# EE192_Sp17_Team01_combo.net
KiCad netlist of a schematic drawn in EAGLE
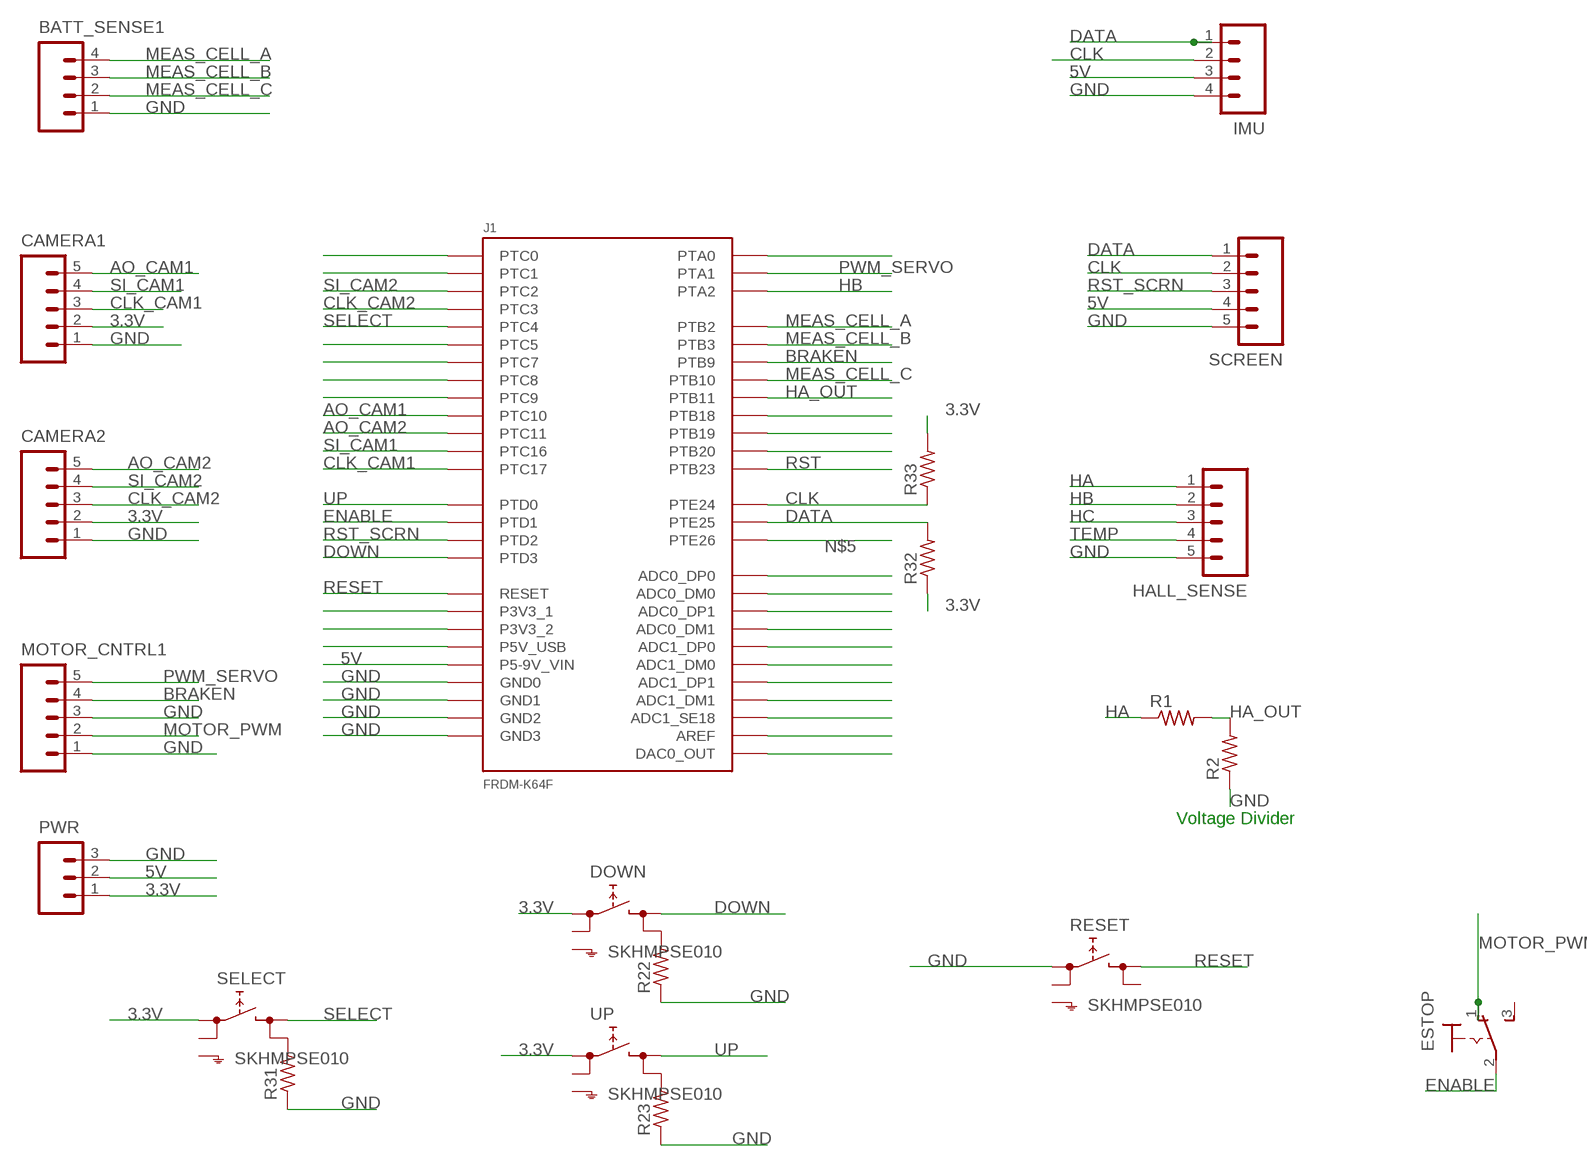
[diagram p0: schematic, sheet 1]
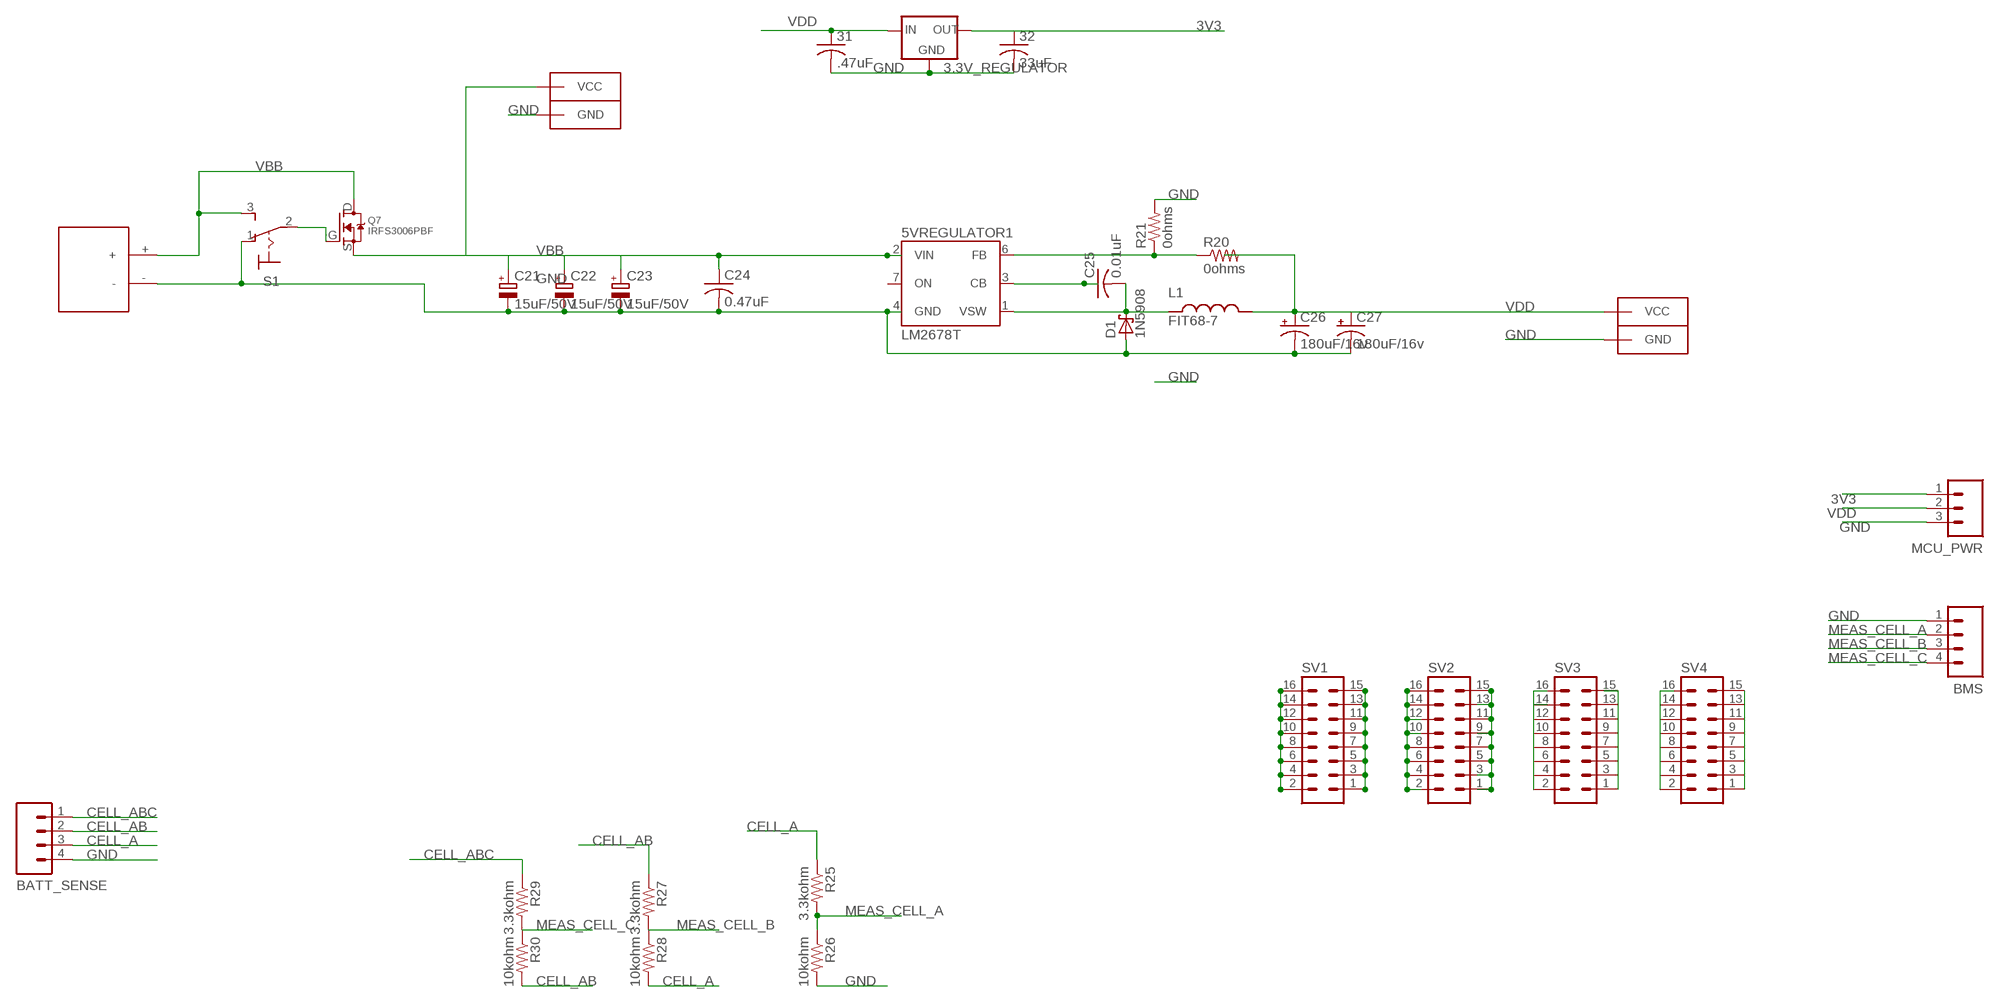
[diagram p1: schematic, sheet 3]
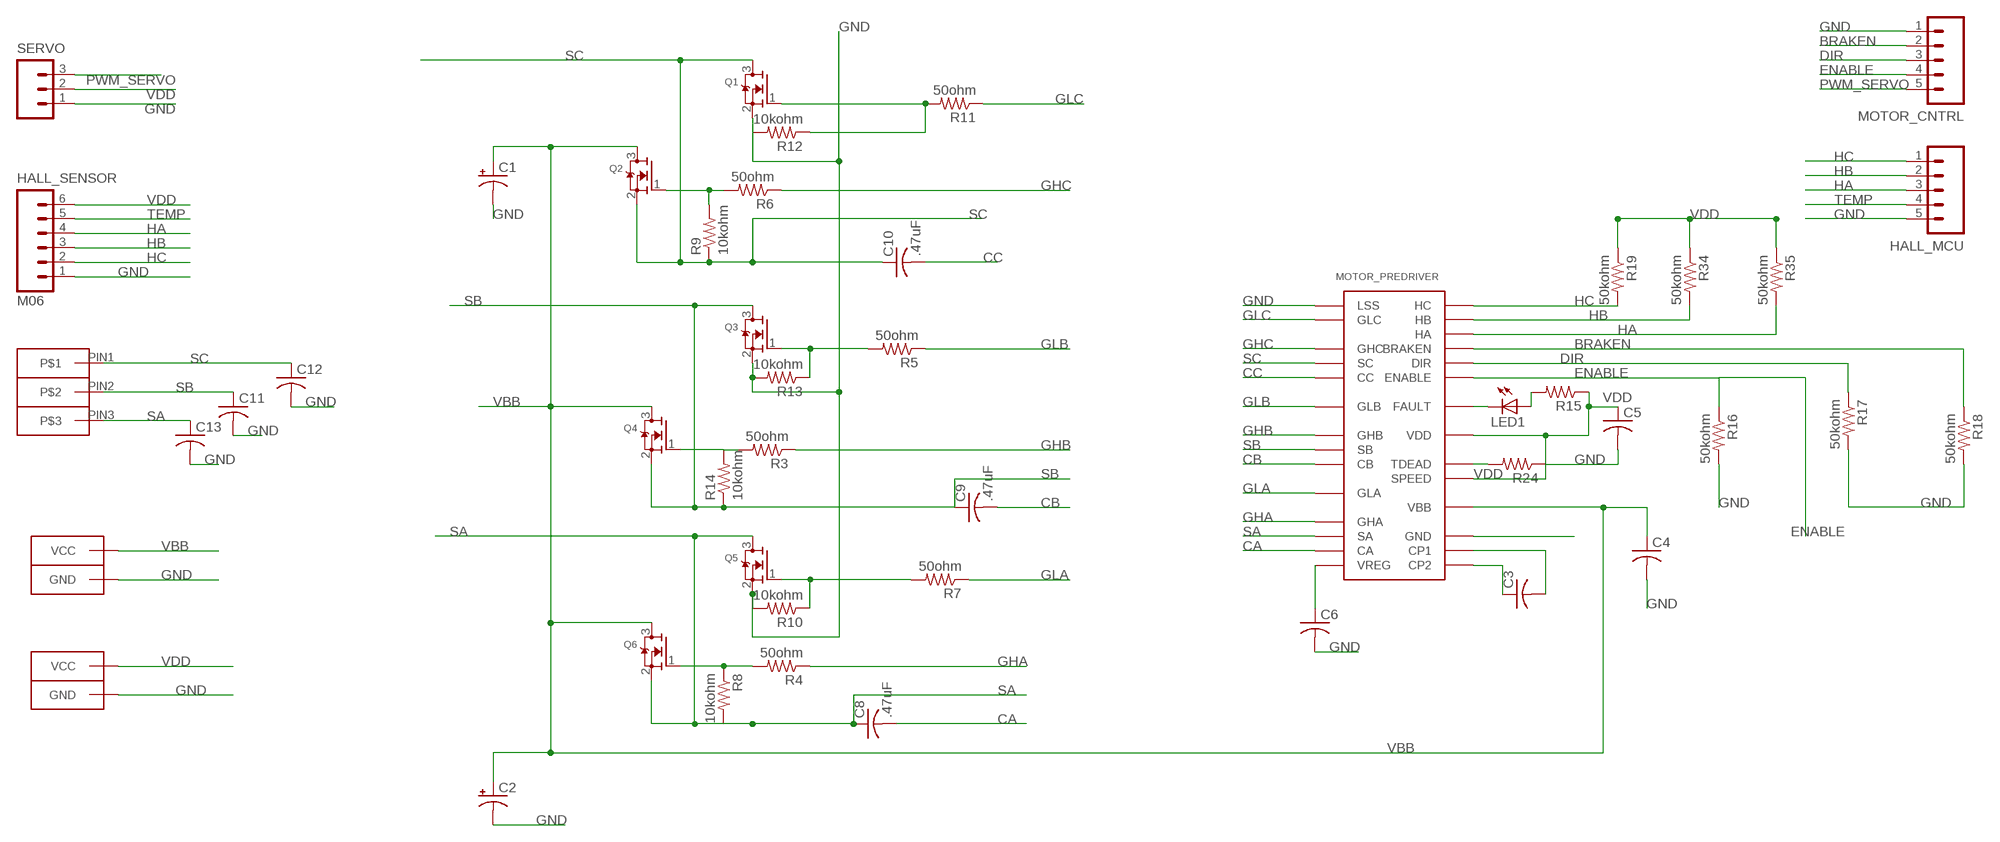
[diagram p2: schematic, sheet 4]

(export (version "E")
  (design (tool "Eeschema 10.0.6"))
  (components
    (comp (ref "C1")
      (value "CPOL-USE5-10.5")
      (footprint "eagle-import:E5-10,5")
      (libsource (lib "eagle-import") (part "CPOL-USE5-10.5"))
    )
    (comp (ref "C2")
      (value "CPOL-USE5-10.5")
      (footprint "eagle-import:E5-10,5")
      (libsource (lib "eagle-import") (part "CPOL-USE5-10.5"))
    )
    (comp (ref "C3")
      (value "C-USC0805")
      (footprint "eagle-import:C0805")
      (libsource (lib "eagle-import") (part "C-USC0805"))
    )
    (comp (ref "C4")
      (value "C-USC0805")
      (footprint "eagle-import:C0805")
      (libsource (lib "eagle-import") (part "C-USC0805"))
    )
    (comp (ref "C5")
      (value "C-USC0805")
      (footprint "eagle-import:C0805")
      (libsource (lib "eagle-import") (part "C-USC0805"))
    )
    (comp (ref "C6")
      (value "C-USC0805")
      (footprint "eagle-import:C0805")
      (libsource (lib "eagle-import") (part "C-USC0805"))
    )
    (comp (ref "C8")
      (value ".47uF")
      (footprint "eagle-import:C0805")
      (libsource (lib "eagle-import") (part "C-USC0805"))
    )
    (comp (ref "C9")
      (value ".47uF")
      (footprint "eagle-import:C0805")
      (libsource (lib "eagle-import") (part "C-USC0805"))
    )
    (comp (ref "C10")
      (value ".47uF")
      (footprint "eagle-import:C0805")
      (libsource (lib "eagle-import") (part "C-USC0805"))
    )
    (comp (ref "C11")
      (value "C-USC0805")
      (footprint "eagle-import:C0805")
      (libsource (lib "eagle-import") (part "C-USC0805"))
    )
    (comp (ref "C12")
      (value "C-USC0805")
      (footprint "eagle-import:C0805")
      (libsource (lib "eagle-import") (part "C-USC0805"))
    )
    (comp (ref "C13")
      (value "C-USC0805")
      (footprint "eagle-import:C0805")
      (libsource (lib "eagle-import") (part "C-USC0805"))
    )
    (comp (ref "CONN1")
      (value "ANDERSON_PP_DOUBLEVERTICAL")
      (footprint "eagle-import:ANDERSON_PP_DOUB_VERT")
      (libsource (lib "eagle-import") (part "ANDERSON_PP_DOUBLEVERTICAL"))
    )
    (comp (ref "CONN3")
      (value "ANDERSON_PP_DOUBLEVERTICAL")
      (footprint "eagle-import:ANDERSON_PP_DOUB_VERT")
      (libsource (lib "eagle-import") (part "ANDERSON_PP_DOUBLEVERTICAL"))
    )
    (comp (ref "HALL_MCU")
      (value "M05MTA")
      (footprint "eagle-import:1X05-MTA")
      (libsource (lib "eagle-import") (part "M05MTA"))
    )
    (comp (ref "HALL_SENSOR")
      (value "M06")
      (footprint "eagle-import:1X06-MTA")
      (libsource (lib "eagle-import") (part "M06"))
    )
    (comp (ref "LED1")
      (value "LEDCHIPLED_0805")
      (footprint "eagle-import:CHIPLED_0805")
      (libsource (lib "eagle-import") (part "LEDCHIPLED_0805"))
    )
    (comp (ref "MOTOR_CNTRL")
      (value "M05MTA")
      (footprint "eagle-import:1X05-MTA")
      (libsource (lib "eagle-import") (part "M05MTA"))
    )
    (comp (ref "MOTOR_PREDRIVER")
      (value "A4915SOCKET")
      (footprint "eagle-import:DIL28-6")
      (libsource (lib "eagle-import") (part "A4915SOCKET"))
    )
    (comp (ref "MOTOR_PWR1")
      (value "ANDERSON_PP_TRIPVERT")
      (footprint "eagle-import:ANDERSON_PP_TRIP_VERT")
      (libsource (lib "eagle-import") (part "ANDERSON_PP_TRIPVERT"))
    )
    (comp (ref "Q1")
      (value "IRFS3006PBFTO263PACKAGE")
      (footprint "eagle-import:TO263")
      (libsource (lib "eagle-import") (part "IRFS3006PBFTO263PACKAGE"))
    )
    (comp (ref "Q2")
      (value "IRFS3006PBFTO263PACKAGE")
      (footprint "eagle-import:TO263")
      (libsource (lib "eagle-import") (part "IRFS3006PBFTO263PACKAGE"))
    )
    (comp (ref "Q3")
      (value "IRFS3006PBFTO263PACKAGE")
      (footprint "eagle-import:TO263")
      (libsource (lib "eagle-import") (part "IRFS3006PBFTO263PACKAGE"))
    )
    (comp (ref "Q4")
      (value "IRFS3006PBFTO263PACKAGE")
      (footprint "eagle-import:TO263")
      (libsource (lib "eagle-import") (part "IRFS3006PBFTO263PACKAGE"))
    )
    (comp (ref "Q5")
      (value "IRFS3006PBFTO263PACKAGE")
      (footprint "eagle-import:TO263")
      (libsource (lib "eagle-import") (part "IRFS3006PBFTO263PACKAGE"))
    )
    (comp (ref "Q6")
      (value "IRFS3006PBFTO263PACKAGE")
      (footprint "eagle-import:TO263")
      (libsource (lib "eagle-import") (part "IRFS3006PBFTO263PACKAGE"))
    )
    (comp (ref "R3")
      (value "50ohm")
      (footprint "eagle-import:R0805")
      (libsource (lib "eagle-import") (part "R-US_R0805"))
    )
    (comp (ref "R4")
      (value "50ohm")
      (footprint "eagle-import:R0805")
      (libsource (lib "eagle-import") (part "R-US_R0805"))
    )
    (comp (ref "R5")
      (value "50ohm")
      (footprint "eagle-import:R0805")
      (libsource (lib "eagle-import") (part "R-US_R0805"))
    )
    (comp (ref "R6")
      (value "50ohm")
      (footprint "eagle-import:R0805")
      (libsource (lib "eagle-import") (part "R-US_R0805"))
    )
    (comp (ref "R7")
      (value "50ohm")
      (footprint "eagle-import:R0805")
      (libsource (lib "eagle-import") (part "R-US_R0805"))
    )
    (comp (ref "R8")
      (value "10kohm")
      (footprint "eagle-import:R0805")
      (libsource (lib "eagle-import") (part "R-US_R0805"))
    )
    (comp (ref "R9")
      (value "10kohm")
      (footprint "eagle-import:R0805")
      (libsource (lib "eagle-import") (part "R-US_R0805"))
    )
    (comp (ref "R10")
      (value "10kohm")
      (footprint "eagle-import:R0805")
      (libsource (lib "eagle-import") (part "R-US_R0805"))
    )
    (comp (ref "R11")
      (value "50ohm")
      (footprint "eagle-import:R0805")
      (libsource (lib "eagle-import") (part "R-US_R0805"))
    )
    (comp (ref "R12")
      (value "10kohm")
      (footprint "eagle-import:R0805")
      (libsource (lib "eagle-import") (part "R-US_R0805"))
    )
    (comp (ref "R13")
      (value "10kohm")
      (footprint "eagle-import:R0805")
      (libsource (lib "eagle-import") (part "R-US_R0805"))
    )
    (comp (ref "R14")
      (value "10kohm")
      (footprint "eagle-import:R0805")
      (libsource (lib "eagle-import") (part "R-US_R0805"))
    )
    (comp (ref "R15")
      (value "R-US_R0805")
      (footprint "eagle-import:R0805")
      (libsource (lib "eagle-import") (part "R-US_R0805"))
    )
    (comp (ref "R16")
      (value "50kohm")
      (footprint "eagle-import:R0805")
      (libsource (lib "eagle-import") (part "R-US_R0805"))
    )
    (comp (ref "R17")
      (value "50kohm")
      (footprint "eagle-import:R0805")
      (libsource (lib "eagle-import") (part "R-US_R0805"))
    )
    (comp (ref "R18")
      (value "50kohm")
      (footprint "eagle-import:R0805")
      (libsource (lib "eagle-import") (part "R-US_R0805"))
    )
    (comp (ref "R19")
      (value "50kohm")
      (footprint "eagle-import:R0805")
      (libsource (lib "eagle-import") (part "R-US_R0805"))
    )
    (comp (ref "R24")
      (value "R-US_R0805")
      (footprint "eagle-import:R0805")
      (libsource (lib "eagle-import") (part "R-US_R0805"))
    )
    (comp (ref "R34")
      (value "50kohm")
      (footprint "eagle-import:R0805")
      (libsource (lib "eagle-import") (part "R-US_R0805"))
    )
    (comp (ref "R35")
      (value "50kohm")
      (footprint "eagle-import:R0805")
      (libsource (lib "eagle-import") (part "R-US_R0805"))
    )
    (comp (ref "SERVO")
      (value "M031X03-MTA")
      (footprint "eagle-import:1X03-MTA")
      (libsource (lib "eagle-import") (part "ee192TomasVersion_M031X03-MTA"))
    )
    (comp (ref "3.3V_REGULATOR")
      (value "78MXXL")
      (footprint "eagle-import:78MXXL")
      (libsource (lib "eagle-import") (part "78MXXL"))
    )
    (comp (ref "5VREGULATOR1")
      (value "LM2678T")
      (footprint "eagle-import:TO220-7")
      (libsource (lib "eagle-import") (part "LM2678T"))
    )
    (comp (ref "31")
      (value ".47uF")
      (footprint "eagle-import:C0805")
      (libsource (lib "eagle-import") (part "C-USC0805"))
    )
    (comp (ref "32")
      (value "33uF")
      (footprint "eagle-import:C0805")
      (libsource (lib "eagle-import") (part "C-USC0805"))
    )
    (comp (ref "BATT_SENSE")
      (value "M041X04-MTA")
      (footprint "eagle-import:1X04-MTA")
      (libsource (lib "eagle-import") (part "M041X04-MTA"))
    )
    (comp (ref "BMS")
      (value "M041X04-MTA")
      (footprint "eagle-import:1X04-MTA")
      (libsource (lib "eagle-import") (part "ee192TomasVersion_M041X04-MTA"))
    )
    (comp (ref "C21")
      (value "15uF/50V")
      (footprint "eagle-import:CT7343")
      (libsource (lib "eagle-import") (part "CPOL-EUCT7343"))
    )
    (comp (ref "C22")
      (value "15uF/50V")
      (footprint "eagle-import:CT7343")
      (libsource (lib "eagle-import") (part "CPOL-EUCT7343"))
    )
    (comp (ref "C23")
      (value "15uF/50V")
      (footprint "eagle-import:CT7343")
      (libsource (lib "eagle-import") (part "CPOL-EUCT7343"))
    )
    (comp (ref "C24")
      (value "0.47uF")
      (footprint "eagle-import:C0805")
      (libsource (lib "eagle-import") (part "C-USC0805"))
    )
    (comp (ref "C25")
      (value "0.01uF")
      (footprint "eagle-import:C0805")
      (libsource (lib "eagle-import") (part "C-USC0805"))
    )
    (comp (ref "C26")
      (value "180uF/16v")
      (footprint "eagle-import:E3,5-8")
      (libsource (lib "eagle-import") (part "CPOL-USE3.5-8"))
    )
    (comp (ref "C27")
      (value "180uF/16v")
      (footprint "eagle-import:E3,5-8")
      (libsource (lib "eagle-import") (part "CPOL-USE3.5-8"))
    )
    (comp (ref "CONN2")
      (value "ANDERSON_PP_DOUBLEVERTICAL")
      (footprint "eagle-import:ANDERSON_PP_DOUB_VERT")
      (libsource (lib "eagle-import") (part "ANDERSON_PP_DOUBLEVERTICAL"))
    )
    (comp (ref "D1")
      (value "1N5908")
      (footprint "eagle-import:C4111-15")
      (libsource (lib "eagle-import") (part "1N5908"))
    )
    (comp (ref "L1")
      (value "FIT68-7")
      (footprint "eagle-import:FIT68-7")
      (libsource (lib "eagle-import") (part "FIT68-7"))
    )
    (comp (ref "MCU_PWR")
      (value "M031X03-MTA")
      (footprint "eagle-import:1X03-MTA")
      (libsource (lib "eagle-import") (part "M031X03-MTA"))
    )
    (comp (ref "MOTOR_PWR")
      (value "ANDERSON_PP_DOUBLEVERTICAL")
      (footprint "eagle-import:ANDERSON_PP_DOUB_VERT")
      (libsource (lib "eagle-import") (part "ANDERSON_PP_DOUBLEVERTICAL"))
    )
    (comp (ref "Q7")
      (value "IRFS3006PBF")
      (footprint "eagle-import:IRFS3006PBF")
      (libsource (lib "eagle-import") (part "ee192TomasVersion_IRFS3006PBF"))
    )
    (comp (ref "R20")
      (value "0ohms")
      (footprint "eagle-import:R0805")
      (libsource (lib "eagle-import") (part "resistor_R-US_R0805"))
    )
    (comp (ref "R21")
      (value "0ohms")
      (footprint "eagle-import:R0805")
      (libsource (lib "eagle-import") (part "resistor_R-US_R0805"))
    )
    (comp (ref "R25")
      (value "3.3kohm")
      (footprint "eagle-import:R0805")
      (libsource (lib "eagle-import") (part "R-US_R0805"))
    )
    (comp (ref "R26")
      (value "10kohm")
      (footprint "eagle-import:R0805")
      (libsource (lib "eagle-import") (part "R-US_R0805"))
    )
    (comp (ref "R27")
      (value "3.3kohm")
      (footprint "eagle-import:R0805")
      (libsource (lib "eagle-import") (part "R-US_R0805"))
    )
    (comp (ref "R28")
      (value "10kohm")
      (footprint "eagle-import:R0805")
      (libsource (lib "eagle-import") (part "R-US_R0805"))
    )
    (comp (ref "R29")
      (value "3.3kohm")
      (footprint "eagle-import:R0805")
      (libsource (lib "eagle-import") (part "R-US_R0805"))
    )
    (comp (ref "R30")
      (value "10kohm")
      (footprint "eagle-import:R0805")
      (libsource (lib "eagle-import") (part "R-US_R0805"))
    )
    (comp (ref "S1")
      (value "320-916")
      (footprint "eagle-import:320-916")
      (libsource (lib "eagle-import") (part "320-916"))
    )
    (comp (ref "SV1")
      (value "MA08-2")
      (footprint "eagle-import:MA08-2")
      (libsource (lib "eagle-import") (part "MA08-2"))
    )
    (comp (ref "SV2")
      (value "MA08-2")
      (footprint "eagle-import:MA08-2")
      (libsource (lib "eagle-import") (part "MA08-2"))
    )
    (comp (ref "SV3")
      (value "MA08-2")
      (footprint "eagle-import:MA08-2")
      (libsource (lib "eagle-import") (part "MA08-2"))
    )
    (comp (ref "SV4")
      (value "MA08-2")
      (footprint "eagle-import:MA08-2")
      (libsource (lib "eagle-import") (part "MA08-2"))
    )
    (comp (ref "U$5")
      (value "TAMIYA")
      (footprint "eagle-import:TAMIYA")
      (libsource (lib "eagle-import") (part "TAMIYA"))
    )
    (comp (ref "BATT_SENSE1")
      (value "M041X04-MTA")
      (footprint "eagle-import:1X04-MTA")
      (libsource (lib "eagle-import") (part "ee192TomasVersion_M041X04-MTA"))
    )
    (comp (ref "CAMERA1")
      (value "M05MTA")
      (footprint "eagle-import:1X05-MTA")
      (libsource (lib "eagle-import") (part "M05MTA"))
    )
    (comp (ref "CAMERA2")
      (value "M05MTA")
      (footprint "eagle-import:1X05-MTA")
      (libsource (lib "eagle-import") (part "M05MTA"))
    )
    (comp (ref "DOWN")
      (value "SKHMPSE010")
      (footprint "eagle-import:SKHMPXE010")
      (libsource (lib "eagle-import") (part "SKHMPE010S"))
    )
    (comp (ref "ESTOP")
      (value "320-916")
      (footprint "eagle-import:320-916")
      (libsource (lib "eagle-import") (part "320-916"))
    )
    (comp (ref "HALL_SENSE")
      (value "M05MTA")
      (footprint "eagle-import:1X05-MTA")
      (libsource (lib "eagle-import") (part "M05MTA"))
    )
    (comp (ref "IMU")
      (value "M041X04-MTA")
      (footprint "eagle-import:1X04-MTA")
      (libsource (lib "eagle-import") (part "ee192TomasVersion_M041X04-MTA"))
    )
    (comp (ref "J1")
      (value "FRDM-K64F")
      (footprint "eagle-import:FRDM-K64F")
      (libsource (lib "eagle-import") (part "FRDM-K64F"))
    )
    (comp (ref "MOTOR_CNTRL1")
      (value "M05MTA")
      (footprint "eagle-import:1X05-MTA")
      (libsource (lib "eagle-import") (part "M05MTA"))
    )
    (comp (ref "PWR")
      (value "M031X03-MTA")
      (footprint "eagle-import:1X03-MTA")
      (libsource (lib "eagle-import") (part "ee192TomasVersion_M031X03-MTA"))
    )
    (comp (ref "R1")
      (value "R-US_R0805")
      (footprint "eagle-import:R0805")
      (libsource (lib "eagle-import") (part "resistor_R-US_R0805"))
    )
    (comp (ref "R2")
      (value "R-US_R0805")
      (footprint "eagle-import:R0805")
      (libsource (lib "eagle-import") (part "resistor_R-US_R0805"))
    )
    (comp (ref "R22")
      (value "R-US_R0805")
      (footprint "eagle-import:R0805")
      (libsource (lib "eagle-import") (part "R-US_R0805"))
    )
    (comp (ref "R23")
      (value "R-US_R0805")
      (footprint "eagle-import:R0805")
      (libsource (lib "eagle-import") (part "R-US_R0805"))
    )
    (comp (ref "R31")
      (value "R-US_R0805")
      (footprint "eagle-import:R0805")
      (libsource (lib "eagle-import") (part "R-US_R0805"))
    )
    (comp (ref "R32")
      (value "R-US_R0805")
      (footprint "eagle-import:R0805")
      (libsource (lib "eagle-import") (part "R-US_R0805"))
    )
    (comp (ref "R33")
      (value "R-US_R0805")
      (footprint "eagle-import:R0805")
      (libsource (lib "eagle-import") (part "R-US_R0805"))
    )
    (comp (ref "RESET")
      (value "SKHMPSE010")
      (footprint "eagle-import:SKHMPXE010")
      (libsource (lib "eagle-import") (part "SKHMPE010S"))
    )
    (comp (ref "SCREEN")
      (value "M05MTA")
      (footprint "eagle-import:1X05-MTA")
      (libsource (lib "eagle-import") (part "M05MTA"))
    )
    (comp (ref "SELECT")
      (value "SKHMPSE010")
      (footprint "eagle-import:SKHMPXE010")
      (libsource (lib "eagle-import") (part "SKHMPE010S"))
    )
    (comp (ref "UP")
      (value "SKHMPSE010")
      (footprint "eagle-import:SKHMPXE010")
      (libsource (lib "eagle-import") (part "SKHMPE010S"))
    )
  )
  (nets
    (net (code "1") (name "3.3V") (class "Default")
      (node (ref "CAMERA1") (pin "2") (pinfunction "2_2") (pintype "passive"))
      (node (ref "CAMERA2") (pin "2") (pinfunction "2_2") (pintype "passive"))
      (node (ref "DOWN") (pin "1") (pinfunction "1.1_1") (pintype "passive"))
      (node (ref "PWR") (pin "1") (pinfunction "1_1") (pintype "passive"))
      (node (ref "R32") (pin "1") (pinfunction "1_1") (pintype "passive"))
      (node (ref "R33") (pin "2") (pinfunction "2_2") (pintype "passive"))
      (node (ref "SELECT") (pin "1") (pinfunction "1.1_1") (pintype "passive"))
      (node (ref "UP") (pin "1") (pinfunction "1.1_1") (pintype "passive"))
    )
    (net (code "2") (name "3V3") (class "Default")
      (node (ref "3.3V_REGULATOR") (pin "OUT") (pinfunction "OUT_OUT") (pintype "passive"))
      (node (ref "32") (pin "1") (pinfunction "1_1") (pintype "passive"))
      (node (ref "MCU_PWR") (pin "1") (pinfunction "1_1") (pintype "passive"))
    )
    (net (code "3") (name "5V") (class "Default")
      (node (ref "IMU") (pin "3") (pinfunction "3_3") (pintype "passive"))
      (node (ref "J1") (pin "J3-16") (pinfunction "P5-9V_VIN_J3-16") (pintype "bidirectional"))
      (node (ref "PWR") (pin "2") (pinfunction "2_2") (pintype "passive"))
      (node (ref "SCREEN") (pin "4") (pinfunction "4_4") (pintype "passive"))
    )
    (net (code "4") (name "AO_CAM1") (class "Default")
      (node (ref "CAMERA1") (pin "5") (pinfunction "5_5") (pintype "passive"))
      (node (ref "J1") (pin "J4-12") (pinfunction "PTC10_J4-12") (pintype "bidirectional"))
    )
    (net (code "5") (name "AO_CAM2") (class "Default")
      (node (ref "CAMERA2") (pin "5") (pinfunction "5_5") (pintype "passive"))
      (node (ref "J1") (pin "J4-10") (pinfunction "PTC11_J4-10") (pintype "bidirectional"))
    )
    (net (code "6") (name "BRAKEN") (class "Default")
      (node (ref "J1") (pin "J1-6") (pinfunction "PTB9_J1-6") (pintype "bidirectional"))
      (node (ref "MOTOR_CNTRL") (pin "2") (pinfunction "2_2") (pintype "passive"))
      (node (ref "MOTOR_CNTRL1") (pin "4") (pinfunction "4_4") (pintype "passive"))
      (node (ref "MOTOR_PREDRIVER") (pin "25") (pinfunction "BRAKEN_25") (pintype "bidirectional"))
      (node (ref "R18") (pin "1") (pinfunction "1_1") (pintype "passive"))
    )
    (net (code "7") (name "CA") (class "Default")
      (node (ref "C8") (pin "2") (pinfunction "2_2") (pintype "passive"))
      (node (ref "MOTOR_PREDRIVER") (pin "13") (pinfunction "CA_13") (pintype "bidirectional"))
    )
    (net (code "8") (name "CB") (class "Default")
      (node (ref "C9") (pin "2") (pinfunction "2_2") (pintype "passive"))
      (node (ref "MOTOR_PREDRIVER") (pin "9") (pinfunction "CB_9") (pintype "bidirectional"))
    )
    (net (code "9") (name "CC") (class "Default")
      (node (ref "C10") (pin "2") (pinfunction "2_2") (pintype "passive"))
      (node (ref "MOTOR_PREDRIVER") (pin "5") (pinfunction "CC_5") (pintype "bidirectional"))
    )
    (net (code "10") (name "CELL_A") (class "Default")
      (node (ref "BATT_SENSE") (pin "3") (pinfunction "3_3") (pintype "passive"))
      (node (ref "R25") (pin "1") (pinfunction "1_1") (pintype "passive"))
      (node (ref "R28") (pin "2") (pinfunction "2_2") (pintype "passive"))
    )
    (net (code "11") (name "CELL_AB") (class "Default")
      (node (ref "BATT_SENSE") (pin "2") (pinfunction "2_2") (pintype "passive"))
      (node (ref "R27") (pin "1") (pinfunction "1_1") (pintype "passive"))
      (node (ref "R30") (pin "2") (pinfunction "2_2") (pintype "passive"))
    )
    (net (code "12") (name "CELL_ABC") (class "Default")
      (node (ref "BATT_SENSE") (pin "1") (pinfunction "1_1") (pintype "passive"))
      (node (ref "R29") (pin "1") (pinfunction "1_1") (pintype "passive"))
    )
    (net (code "13") (name "CLK") (class "Default")
      (node (ref "IMU") (pin "2") (pinfunction "2_2") (pintype "passive"))
      (node (ref "J1") (pin "J2-20") (pinfunction "PTE24_J2-20") (pintype "bidirectional"))
      (node (ref "R33") (pin "1") (pinfunction "1_1") (pintype "passive"))
      (node (ref "SCREEN") (pin "2") (pinfunction "2_2") (pintype "passive"))
    )
    (net (code "14") (name "CLK_CAM1") (class "Default")
      (node (ref "CAMERA1") (pin "3") (pinfunction "3_3") (pintype "passive"))
      (node (ref "J1") (pin "J1-4") (pinfunction "PTC17_J1-4") (pintype "bidirectional"))
    )
    (net (code "15") (name "CLK_CAM2") (class "Default")
      (node (ref "CAMERA2") (pin "3") (pinfunction "3_3") (pintype "passive"))
      (node (ref "J1") (pin "J1-16") (pinfunction "PTC3_J1-16") (pintype "bidirectional"))
    )
    (net (code "16") (name "DATA") (class "Default")
      (node (ref "IMU") (pin "1") (pinfunction "1_1") (pintype "passive"))
      (node (ref "J1") (pin "J2-18") (pinfunction "PTE25_J2-18") (pintype "bidirectional"))
      (node (ref "R32") (pin "2") (pinfunction "2_2") (pintype "passive"))
      (node (ref "SCREEN") (pin "1") (pinfunction "1_1") (pintype "passive"))
    )
    (net (code "17") (name "DIR") (class "Default")
      (node (ref "MOTOR_CNTRL") (pin "3") (pinfunction "3_3") (pintype "passive"))
      (node (ref "MOTOR_PREDRIVER") (pin "24") (pinfunction "DIR_24") (pintype "bidirectional"))
      (node (ref "R17") (pin "1") (pinfunction "1_1") (pintype "passive"))
    )
    (net (code "18") (name "DOWN") (class "Default")
      (node (ref "DOWN") (pin "3") (pinfunction "2.1_3") (pintype "passive"))
      (node (ref "J1") (pin "J2-10") (pinfunction "PTD3_J2-10") (pintype "bidirectional"))
    )
    (net (code "19") (name "ENABLE") (class "Default")
      (node (ref "ESTOP") (pin "2") (pinfunction "P_2") (pintype "passive"))
      (node (ref "J1") (pin "J2-12") (pinfunction "PTD1_J2-12") (pintype "bidirectional"))
      (node (ref "MOTOR_CNTRL") (pin "4") (pinfunction "4_4") (pintype "passive"))
      (node (ref "MOTOR_PREDRIVER") (pin "23") (pinfunction "ENABLE_23") (pintype "bidirectional"))
      (node (ref "R16") (pin "1") (pinfunction "1_1") (pintype "passive"))
    )
    (net (code "20") (name "GHA") (class "Default")
      (node (ref "MOTOR_PREDRIVER") (pin "11") (pinfunction "GHA_11") (pintype "bidirectional"))
      (node (ref "R4") (pin "1") (pinfunction "1_1") (pintype "passive"))
    )
    (net (code "21") (name "GHB") (class "Default")
      (node (ref "MOTOR_PREDRIVER") (pin "7") (pinfunction "GHB_7") (pintype "bidirectional"))
      (node (ref "R3") (pin "1") (pinfunction "1_1") (pintype "passive"))
    )
    (net (code "22") (name "GHC") (class "Default")
      (node (ref "MOTOR_PREDRIVER") (pin "3") (pinfunction "GHC_3") (pintype "bidirectional"))
      (node (ref "R6") (pin "1") (pinfunction "1_1") (pintype "passive"))
    )
    (net (code "23") (name "GLA") (class "Default")
      (node (ref "MOTOR_PREDRIVER") (pin "10") (pinfunction "GLA_10") (pintype "bidirectional"))
      (node (ref "R7") (pin "1") (pinfunction "1_1") (pintype "passive"))
    )
    (net (code "24") (name "GLB") (class "Default")
      (node (ref "MOTOR_PREDRIVER") (pin "6") (pinfunction "GLB_6") (pintype "bidirectional"))
      (node (ref "R5") (pin "1") (pinfunction "1_1") (pintype "passive"))
    )
    (net (code "25") (name "GLC") (class "Default")
      (node (ref "MOTOR_PREDRIVER") (pin "2") (pinfunction "GLC_2") (pintype "bidirectional"))
      (node (ref "R11") (pin "1") (pinfunction "1_1") (pintype "passive"))
    )
    (net (code "26") (name "GND") (class "Default")
      (node (ref "3.3V_REGULATOR") (pin "GND") (pinfunction "GND_GND") (pintype "input"))
      (node (ref "31") (pin "2") (pinfunction "2_2") (pintype "passive"))
      (node (ref "32") (pin "2") (pinfunction "2_2") (pintype "passive"))
      (node (ref "5VREGULATOR1") (pin "4") (pinfunction "GND_4") (pintype "power_in"))
      (node (ref "BATT_SENSE") (pin "4") (pinfunction "4_4") (pintype "passive"))
      (node (ref "BATT_SENSE1") (pin "1") (pinfunction "1_1") (pintype "passive"))
      (node (ref "BMS") (pin "1") (pinfunction "1_1") (pintype "passive"))
      (node (ref "C1") (pin "-") (pinfunction "-_-") (pintype "passive"))
      (node (ref "C11") (pin "2") (pinfunction "2_2") (pintype "passive"))
      (node (ref "C12") (pin "2") (pinfunction "2_2") (pintype "passive"))
      (node (ref "C13") (pin "2") (pinfunction "2_2") (pintype "passive"))
      (node (ref "C2") (pin "-") (pinfunction "-_-") (pintype "passive"))
      (node (ref "C21") (pin "-") (pinfunction "-_-") (pintype "passive"))
      (node (ref "C22") (pin "-") (pinfunction "-_-") (pintype "passive"))
      (node (ref "C23") (pin "-") (pinfunction "-_-") (pintype "passive"))
      (node (ref "C24") (pin "2") (pinfunction "2_2") (pintype "passive"))
      (node (ref "C26") (pin "-") (pinfunction "-_-") (pintype "passive"))
      (node (ref "C27") (pin "-") (pinfunction "-_-") (pintype "passive"))
      (node (ref "C4") (pin "2") (pinfunction "2_2") (pintype "passive"))
      (node (ref "C5") (pin "2") (pinfunction "2_2") (pintype "passive"))
      (node (ref "C6") (pin "2") (pinfunction "2_2") (pintype "passive"))
      (node (ref "CAMERA1") (pin "1") (pinfunction "1_1") (pintype "passive"))
      (node (ref "CAMERA2") (pin "1") (pinfunction "1_1") (pintype "passive"))
      (node (ref "CONN1") (pin "PIN1") (pinfunction "GND_PIN1") (pintype "bidirectional"))
      (node (ref "CONN2") (pin "PIN1") (pinfunction "GND_PIN1") (pintype "bidirectional"))
      (node (ref "CONN3") (pin "PIN1") (pinfunction "GND_PIN1") (pintype "bidirectional"))
      (node (ref "D1") (pin "A") (pinfunction "A_A") (pintype "passive"))
      (node (ref "HALL_MCU") (pin "5") (pinfunction "5_5") (pintype "passive"))
      (node (ref "HALL_SENSE") (pin "5") (pinfunction "5_5") (pintype "passive"))
      (node (ref "HALL_SENSOR") (pin "1") (pinfunction "1_1") (pintype "passive"))
      (node (ref "IMU") (pin "4") (pinfunction "4_4") (pintype "passive"))
      (node (ref "J1") (pin "J2-14") (pinfunction "GND1_J2-14") (pintype "bidirectional"))
      (node (ref "J1") (pin "J2-3") (pinfunction "GND0_J2-3") (pintype "bidirectional"))
      (node (ref "J1") (pin "J3-12") (pinfunction "GND2_J3-12") (pintype "bidirectional"))
      (node (ref "J1") (pin "J3-14") (pinfunction "GND3_J3-14") (pintype "bidirectional"))
      (node (ref "MCU_PWR") (pin "3") (pinfunction "3_3") (pintype "passive"))
      (node (ref "MOTOR_CNTRL") (pin "1") (pinfunction "1_1") (pintype "passive"))
      (node (ref "MOTOR_CNTRL1") (pin "1") (pinfunction "1_1") (pintype "passive"))
      (node (ref "MOTOR_CNTRL1") (pin "3") (pinfunction "3_3") (pintype "passive"))
      (node (ref "MOTOR_PREDRIVER") (pin "1") (pinfunction "LSS_1") (pintype "bidirectional"))
      (node (ref "MOTOR_PWR") (pin "PIN1") (pinfunction "GND_PIN1") (pintype "bidirectional"))
      (node (ref "PWR") (pin "3") (pinfunction "3_3") (pintype "passive"))
      (node (ref "Q1") (pin "2") (pinfunction "S_2") (pintype "bidirectional"))
      (node (ref "Q3") (pin "2") (pinfunction "S_2") (pintype "bidirectional"))
      (node (ref "Q5") (pin "2") (pinfunction "S_2") (pintype "bidirectional"))
      (node (ref "R10") (pin "2") (pinfunction "2_2") (pintype "passive"))
      (node (ref "R12") (pin "2") (pinfunction "2_2") (pintype "passive"))
      (node (ref "R13") (pin "2") (pinfunction "2_2") (pintype "passive"))
      (node (ref "R16") (pin "2") (pinfunction "2_2") (pintype "passive"))
      (node (ref "R17") (pin "2") (pinfunction "2_2") (pintype "passive"))
      (node (ref "R18") (pin "2") (pinfunction "2_2") (pintype "passive"))
      (node (ref "R2") (pin "1") (pinfunction "1_1") (pintype "passive"))
      (node (ref "R21") (pin "2") (pinfunction "2_2") (pintype "passive"))
      (node (ref "R22") (pin "1") (pinfunction "1_1") (pintype "passive"))
      (node (ref "R23") (pin "1") (pinfunction "1_1") (pintype "passive"))
      (node (ref "R24") (pin "1") (pinfunction "1_1") (pintype "passive"))
      (node (ref "R26") (pin "2") (pinfunction "2_2") (pintype "passive"))
      (node (ref "R31") (pin "1") (pinfunction "1_1") (pintype "passive"))
      (node (ref "RESET") (pin "1") (pinfunction "1.1_1") (pintype "passive"))
      (node (ref "S1") (pin "1") (pinfunction "O_1") (pintype "passive"))
      (node (ref "SCREEN") (pin "5") (pinfunction "5_5") (pintype "passive"))
      (node (ref "SERVO") (pin "1") (pinfunction "1_1") (pintype "passive"))
      (node (ref "U$5") (pin "-") (pinfunction "-_-") (pintype "bidirectional"))
    )
    (net (code "27") (name "HA") (class "Default")
      (node (ref "HALL_MCU") (pin "3") (pinfunction "3_3") (pintype "passive"))
      (node (ref "HALL_SENSE") (pin "1") (pinfunction "1_1") (pintype "passive"))
      (node (ref "HALL_SENSOR") (pin "4") (pinfunction "4_4") (pintype "passive"))
      (node (ref "MOTOR_PREDRIVER") (pin "26") (pinfunction "HA_26") (pintype "bidirectional"))
      (node (ref "R1") (pin "1") (pinfunction "1_1") (pintype "passive"))
      (node (ref "R35") (pin "2") (pinfunction "2_2") (pintype "passive"))
    )
    (net (code "28") (name "HA_OUT") (class "Default")
      (node (ref "J1") (pin "J4-8") (pinfunction "PTB11_J4-8") (pintype "bidirectional"))
      (node (ref "R1") (pin "2") (pinfunction "2_2") (pintype "passive"))
      (node (ref "R2") (pin "2") (pinfunction "2_2") (pintype "passive"))
    )
    (net (code "29") (name "HB") (class "Default")
      (node (ref "HALL_MCU") (pin "2") (pinfunction "2_2") (pintype "passive"))
      (node (ref "HALL_SENSE") (pin "2") (pinfunction "2_2") (pintype "passive"))
      (node (ref "HALL_SENSOR") (pin "3") (pinfunction "3_3") (pintype "passive"))
      (node (ref "J1") (pin "J1-12") (pinfunction "PTA2_J1-12") (pintype "bidirectional"))
      (node (ref "MOTOR_PREDRIVER") (pin "27") (pinfunction "HB_27") (pintype "bidirectional"))
      (node (ref "R34") (pin "2") (pinfunction "2_2") (pintype "passive"))
    )
    (net (code "30") (name "HC") (class "Default")
      (node (ref "HALL_MCU") (pin "1") (pinfunction "1_1") (pintype "passive"))
      (node (ref "HALL_SENSE") (pin "3") (pinfunction "3_3") (pintype "passive"))
      (node (ref "HALL_SENSOR") (pin "2") (pinfunction "2_2") (pintype "passive"))
      (node (ref "MOTOR_PREDRIVER") (pin "28") (pinfunction "HC_28") (pintype "bidirectional"))
      (node (ref "R19") (pin "2") (pinfunction "2_2") (pintype "passive"))
    )
    (net (code "31") (name "MEAS_CELL_A") (class "Default")
      (node (ref "BATT_SENSE1") (pin "4") (pinfunction "4_4") (pintype "passive"))
      (node (ref "BMS") (pin "2") (pinfunction "2_2") (pintype "passive"))
      (node (ref "J1") (pin "J4-2") (pinfunction "PTB2_J4-2") (pintype "bidirectional"))
      (node (ref "R25") (pin "2") (pinfunction "2_2") (pintype "passive"))
      (node (ref "R26") (pin "1") (pinfunction "1_1") (pintype "passive"))
    )
    (net (code "32") (name "MEAS_CELL_B") (class "Default")
      (node (ref "BATT_SENSE1") (pin "3") (pinfunction "3_3") (pintype "passive"))
      (node (ref "BMS") (pin "3") (pinfunction "3_3") (pintype "passive"))
      (node (ref "J1") (pin "J4-4") (pinfunction "PTB3_J4-4") (pintype "bidirectional"))
      (node (ref "R27") (pin "2") (pinfunction "2_2") (pintype "passive"))
      (node (ref "R28") (pin "1") (pinfunction "1_1") (pintype "passive"))
    )
    (net (code "33") (name "MEAS_CELL_C") (class "Default")
      (node (ref "BATT_SENSE1") (pin "2") (pinfunction "2_2") (pintype "passive"))
      (node (ref "BMS") (pin "4") (pinfunction "4_4") (pintype "passive"))
      (node (ref "J1") (pin "J4-6") (pinfunction "PTB10_J4-6") (pintype "bidirectional"))
      (node (ref "R29") (pin "2") (pinfunction "2_2") (pintype "passive"))
      (node (ref "R30") (pin "1") (pinfunction "1_1") (pintype "passive"))
    )
    (net (code "34") (name "MOTOR_PWM") (class "Default")
      (node (ref "ESTOP") (pin "1") (pinfunction "O_1") (pintype "passive"))
      (node (ref "MOTOR_CNTRL1") (pin "2") (pinfunction "2_2") (pintype "passive"))
    )
    (net (code "35") (name "N$5") (class "Default")
      (node (ref "J1") (pin "J2-1") (pinfunction "PTE26_J2-1") (pintype "bidirectional"))
    )
    (net (code "36") (name "Net-(5VREGULATOR1-CB)") (class "Default")
      (node (ref "5VREGULATOR1") (pin "3") (pinfunction "CB_3") (pintype "input"))
      (node (ref "C25") (pin "1") (pinfunction "1_1") (pintype "passive"))
    )
    (net (code "37") (name "Net-(5VREGULATOR1-FB)") (class "Default")
      (node (ref "5VREGULATOR1") (pin "6") (pinfunction "FB_6") (pintype "input"))
      (node (ref "R20") (pin "1") (pinfunction "1_1") (pintype "passive"))
      (node (ref "R21") (pin "1") (pinfunction "1_1") (pintype "passive"))
    )
    (net (code "38") (name "Net-(5VREGULATOR1-VSW)") (class "Default")
      (node (ref "5VREGULATOR1") (pin "1") (pinfunction "VSW_1") (pintype "output"))
      (node (ref "C25") (pin "2") (pinfunction "2_2") (pintype "passive"))
      (node (ref "D1") (pin "C") (pinfunction "C_C") (pintype "passive"))
      (node (ref "L1") (pin "P$1") (pinfunction "P$1_P$1") (pintype "bidirectional"))
    )
    (net (code "39") (name "Net-(DOWN-2.2)") (class "Default")
      (node (ref "DOWN") (pin "4") (pinfunction "2.2_4") (pintype "passive"))
      (node (ref "R22") (pin "2") (pinfunction "2_2") (pintype "passive"))
    )
    (net (code "40") (name "Net-(LED1-PadA)") (class "Default")
      (node (ref "LED1") (pin "A") (pinfunction "A_A") (pintype "passive"))
      (node (ref "R15") (pin "2") (pinfunction "2_2") (pintype "passive"))
    )
    (net (code "41") (name "Net-(MOTOR_PREDRIVER-CP1)") (class "Default")
      (node (ref "C3") (pin "2") (pinfunction "2_2") (pintype "passive"))
      (node (ref "MOTOR_PREDRIVER") (pin "16") (pinfunction "CP1_16") (pintype "bidirectional"))
    )
    (net (code "42") (name "Net-(MOTOR_PREDRIVER-CP2)") (class "Default")
      (node (ref "C3") (pin "1") (pinfunction "1_1") (pintype "passive"))
      (node (ref "MOTOR_PREDRIVER") (pin "15") (pinfunction "CP2_15") (pintype "bidirectional"))
    )
    (net (code "43") (name "Net-(MOTOR_PREDRIVER-FAULT)") (class "Default")
      (node (ref "LED1") (pin "C") (pinfunction "C_C") (pintype "passive"))
      (node (ref "MOTOR_PREDRIVER") (pin "22") (pinfunction "FAULT_22") (pintype "bidirectional"))
    )
    (net (code "44") (name "Net-(MOTOR_PREDRIVER-TDEAD)") (class "Default")
      (node (ref "MOTOR_PREDRIVER") (pin "20") (pinfunction "TDEAD_20") (pintype "bidirectional"))
      (node (ref "R24") (pin "2") (pinfunction "2_2") (pintype "passive"))
    )
    (net (code "45") (name "Net-(MOTOR_PREDRIVER-VREG)") (class "Default")
      (node (ref "C6") (pin "1") (pinfunction "1_1") (pintype "passive"))
      (node (ref "MOTOR_PREDRIVER") (pin "14") (pinfunction "VREG_14") (pintype "bidirectional"))
    )
    (net (code "46") (name "Net-(Q1-G)") (class "Default")
      (node (ref "Q1") (pin "1") (pinfunction "G_1") (pintype "bidirectional"))
      (node (ref "R11") (pin "2") (pinfunction "2_2") (pintype "passive"))
      (node (ref "R12") (pin "1") (pinfunction "1_1") (pintype "passive"))
    )
    (net (code "47") (name "Net-(Q2-G)") (class "Default")
      (node (ref "Q2") (pin "1") (pinfunction "G_1") (pintype "bidirectional"))
      (node (ref "R6") (pin "2") (pinfunction "2_2") (pintype "passive"))
      (node (ref "R9") (pin "2") (pinfunction "2_2") (pintype "passive"))
    )
    (net (code "48") (name "Net-(Q3-G)") (class "Default")
      (node (ref "Q3") (pin "1") (pinfunction "G_1") (pintype "bidirectional"))
      (node (ref "R13") (pin "1") (pinfunction "1_1") (pintype "passive"))
      (node (ref "R5") (pin "2") (pinfunction "2_2") (pintype "passive"))
    )
    (net (code "49") (name "Net-(Q4-G)") (class "Default")
      (node (ref "Q4") (pin "1") (pinfunction "G_1") (pintype "bidirectional"))
      (node (ref "R14") (pin "2") (pinfunction "2_2") (pintype "passive"))
      (node (ref "R3") (pin "2") (pinfunction "2_2") (pintype "passive"))
    )
    (net (code "50") (name "Net-(Q5-G)") (class "Default")
      (node (ref "Q5") (pin "1") (pinfunction "G_1") (pintype "bidirectional"))
      (node (ref "R10") (pin "1") (pinfunction "1_1") (pintype "passive"))
      (node (ref "R7") (pin "2") (pinfunction "2_2") (pintype "passive"))
    )
    (net (code "51") (name "Net-(Q6-G)") (class "Default")
      (node (ref "Q6") (pin "1") (pinfunction "G_1") (pintype "bidirectional"))
      (node (ref "R4") (pin "2") (pinfunction "2_2") (pintype "passive"))
      (node (ref "R8") (pin "1") (pinfunction "1_1") (pintype "passive"))
    )
    (net (code "52") (name "Net-(S1-P)") (class "Default")
      (node (ref "Q7") (pin "G") (pinfunction "G_G") (pintype "bidirectional"))
      (node (ref "S1") (pin "2") (pinfunction "P_2") (pintype "passive"))
    )
    (net (code "53") (name "Net-(SELECT-2.2)") (class "Default")
      (node (ref "R31") (pin "2") (pinfunction "2_2") (pintype "passive"))
      (node (ref "SELECT") (pin "4") (pinfunction "2.2_4") (pintype "passive"))
    )
    (net (code "54") (name "Net-(SV1-Pad1)") (class "Default")
      (node (ref "SV1") (pin "1") (pinfunction "1_1") (pintype "passive"))
      (node (ref "SV1") (pin "11") (pinfunction "11_11") (pintype "passive"))
      (node (ref "SV1") (pin "13") (pinfunction "13_13") (pintype "passive"))
      (node (ref "SV1") (pin "15") (pinfunction "15_15") (pintype "passive"))
      (node (ref "SV1") (pin "3") (pinfunction "3_3") (pintype "passive"))
      (node (ref "SV1") (pin "5") (pinfunction "5_5") (pintype "passive"))
      (node (ref "SV1") (pin "7") (pinfunction "7_7") (pintype "passive"))
      (node (ref "SV1") (pin "9") (pinfunction "9_9") (pintype "passive"))
    )
    (net (code "55") (name "Net-(SV1-Pad10)") (class "Default")
      (node (ref "SV1") (pin "10") (pinfunction "10_10") (pintype "passive"))
      (node (ref "SV1") (pin "12") (pinfunction "12_12") (pintype "passive"))
      (node (ref "SV1") (pin "14") (pinfunction "14_14") (pintype "passive"))
      (node (ref "SV1") (pin "16") (pinfunction "16_16") (pintype "passive"))
      (node (ref "SV1") (pin "2") (pinfunction "2_2") (pintype "passive"))
      (node (ref "SV1") (pin "4") (pinfunction "4_4") (pintype "passive"))
      (node (ref "SV1") (pin "6") (pinfunction "6_6") (pintype "passive"))
      (node (ref "SV1") (pin "8") (pinfunction "8_8") (pintype "passive"))
    )
    (net (code "56") (name "Net-(SV2-Pad1)") (class "Default")
      (node (ref "SV2") (pin "1") (pinfunction "1_1") (pintype "passive"))
      (node (ref "SV2") (pin "11") (pinfunction "11_11") (pintype "passive"))
      (node (ref "SV2") (pin "13") (pinfunction "13_13") (pintype "passive"))
      (node (ref "SV2") (pin "15") (pinfunction "15_15") (pintype "passive"))
      (node (ref "SV2") (pin "3") (pinfunction "3_3") (pintype "passive"))
      (node (ref "SV2") (pin "5") (pinfunction "5_5") (pintype "passive"))
      (node (ref "SV2") (pin "7") (pinfunction "7_7") (pintype "passive"))
      (node (ref "SV2") (pin "9") (pinfunction "9_9") (pintype "passive"))
    )
    (net (code "57") (name "Net-(SV2-Pad10)") (class "Default")
      (node (ref "SV2") (pin "10") (pinfunction "10_10") (pintype "passive"))
      (node (ref "SV2") (pin "12") (pinfunction "12_12") (pintype "passive"))
      (node (ref "SV2") (pin "14") (pinfunction "14_14") (pintype "passive"))
      (node (ref "SV2") (pin "16") (pinfunction "16_16") (pintype "passive"))
      (node (ref "SV2") (pin "2") (pinfunction "2_2") (pintype "passive"))
      (node (ref "SV2") (pin "4") (pinfunction "4_4") (pintype "passive"))
      (node (ref "SV2") (pin "6") (pinfunction "6_6") (pintype "passive"))
      (node (ref "SV2") (pin "8") (pinfunction "8_8") (pintype "passive"))
    )
    (net (code "58") (name "Net-(SV3-Pad1)") (class "Default")
      (node (ref "SV3") (pin "1") (pinfunction "1_1") (pintype "passive"))
      (node (ref "SV3") (pin "15") (pinfunction "15_15") (pintype "passive"))
    )
    (net (code "59") (name "Net-(SV3-Pad16)") (class "Default")
      (node (ref "SV3") (pin "16") (pinfunction "16_16") (pintype "passive"))
      (node (ref "SV3") (pin "2") (pinfunction "2_2") (pintype "passive"))
    )
    (net (code "60") (name "Net-(SV4-Pad1)") (class "Default")
      (node (ref "SV4") (pin "1") (pinfunction "1_1") (pintype "passive"))
      (node (ref "SV4") (pin "15") (pinfunction "15_15") (pintype "passive"))
    )
    (net (code "61") (name "Net-(SV4-Pad16)") (class "Default")
      (node (ref "SV4") (pin "16") (pinfunction "16_16") (pintype "passive"))
      (node (ref "SV4") (pin "2") (pinfunction "2_2") (pintype "passive"))
    )
    (net (code "62") (name "Net-(UP-2.2)") (class "Default")
      (node (ref "R23") (pin "2") (pinfunction "2_2") (pintype "passive"))
      (node (ref "UP") (pin "4") (pinfunction "2.2_4") (pintype "passive"))
    )
    (net (code "63") (name "PWM_SERVO") (class "Default")
      (node (ref "J1") (pin "J1-8") (pinfunction "PTA1_J1-8") (pintype "bidirectional"))
      (node (ref "MOTOR_CNTRL") (pin "5") (pinfunction "5_5") (pintype "passive"))
      (node (ref "MOTOR_CNTRL1") (pin "5") (pinfunction "5_5") (pintype "passive"))
      (node (ref "SERVO") (pin "3") (pinfunction "3_3") (pintype "passive"))
    )
    (net (code "64") (name "RESET") (class "Default")
      (node (ref "J1") (pin "J3-6") (pinfunction "RESET_J3-6") (pintype "bidirectional"))
      (node (ref "RESET") (pin "3") (pinfunction "2.1_3") (pintype "passive"))
    )
    (net (code "65") (name "RST") (class "Default")
      (node (ref "J1") (pin "J1-10") (pinfunction "PTB23_J1-10") (pintype "bidirectional"))
    )
    (net (code "66") (name "RST_SCRN") (class "Default")
      (node (ref "J1") (pin "J2-8") (pinfunction "PTD2_J2-8") (pintype "bidirectional"))
      (node (ref "SCREEN") (pin "3") (pinfunction "3_3") (pintype "passive"))
    )
    (net (code "67") (name "SA") (class "Default")
      (node (ref "C13") (pin "1") (pinfunction "1_1") (pintype "passive"))
      (node (ref "C8") (pin "1") (pinfunction "1_1") (pintype "passive"))
      (node (ref "MOTOR_PREDRIVER") (pin "12") (pinfunction "SA_12") (pintype "bidirectional"))
      (node (ref "MOTOR_PWR1") (pin "PIN3") (pinfunction "P$3_PIN3") (pintype "bidirectional"))
      (node (ref "Q5") (pin "3") (pinfunction "D_3") (pintype "bidirectional"))
      (node (ref "Q6") (pin "2") (pinfunction "S_2") (pintype "bidirectional"))
      (node (ref "R8") (pin "2") (pinfunction "2_2") (pintype "passive"))
    )
    (net (code "68") (name "SB") (class "Default")
      (node (ref "C11") (pin "1") (pinfunction "1_1") (pintype "passive"))
      (node (ref "C9") (pin "1") (pinfunction "1_1") (pintype "passive"))
      (node (ref "MOTOR_PREDRIVER") (pin "8") (pinfunction "SB_8") (pintype "bidirectional"))
      (node (ref "MOTOR_PWR1") (pin "PIN2") (pinfunction "P$2_PIN2") (pintype "bidirectional"))
      (node (ref "Q3") (pin "3") (pinfunction "D_3") (pintype "bidirectional"))
      (node (ref "Q4") (pin "2") (pinfunction "S_2") (pintype "bidirectional"))
      (node (ref "R14") (pin "1") (pinfunction "1_1") (pintype "passive"))
    )
    (net (code "69") (name "SC") (class "Default")
      (node (ref "C10") (pin "1") (pinfunction "1_1") (pintype "passive"))
      (node (ref "C12") (pin "1") (pinfunction "1_1") (pintype "passive"))
      (node (ref "MOTOR_PREDRIVER") (pin "4") (pinfunction "SC_4") (pintype "bidirectional"))
      (node (ref "MOTOR_PWR1") (pin "PIN1") (pinfunction "P$1_PIN1") (pintype "bidirectional"))
      (node (ref "Q1") (pin "3") (pinfunction "D_3") (pintype "bidirectional"))
      (node (ref "Q2") (pin "2") (pinfunction "S_2") (pintype "bidirectional"))
      (node (ref "R9") (pin "1") (pinfunction "1_1") (pintype "passive"))
    )
    (net (code "70") (name "SELECT") (class "Default")
      (node (ref "J1") (pin "J2-4") (pinfunction "PTC4_J2-4") (pintype "bidirectional"))
      (node (ref "SELECT") (pin "3") (pinfunction "2.1_3") (pintype "passive"))
    )
    (net (code "71") (name "SI_CAM1") (class "Default")
      (node (ref "CAMERA1") (pin "4") (pinfunction "4_4") (pintype "passive"))
      (node (ref "J1") (pin "J1-2") (pinfunction "PTC16_J1-2") (pintype "bidirectional"))
    )
    (net (code "72") (name "SI_CAM2") (class "Default")
      (node (ref "CAMERA2") (pin "4") (pinfunction "4_4") (pintype "passive"))
      (node (ref "J1") (pin "J1-14") (pinfunction "PTC2_J1-14") (pintype "bidirectional"))
    )
    (net (code "73") (name "TEMP") (class "Default")
      (node (ref "HALL_MCU") (pin "4") (pinfunction "4_4") (pintype "passive"))
      (node (ref "HALL_SENSE") (pin "4") (pinfunction "4_4") (pintype "passive"))
      (node (ref "HALL_SENSOR") (pin "5") (pinfunction "5_5") (pintype "passive"))
    )
    (net (code "74") (name "UP") (class "Default")
      (node (ref "J1") (pin "J2-6") (pinfunction "PTD0_J2-6") (pintype "bidirectional"))
      (node (ref "UP") (pin "3") (pinfunction "2.1_3") (pintype "passive"))
    )
    (net (code "75") (name "VBB") (class "Default")
      (node (ref "5VREGULATOR1") (pin "2") (pinfunction "VIN_2") (pintype "power_in"))
      (node (ref "C1") (pin "+") (pinfunction "+_+") (pintype "passive"))
      (node (ref "C2") (pin "+") (pinfunction "+_+") (pintype "passive"))
      (node (ref "C21") (pin "+") (pinfunction "+_+") (pintype "passive"))
      (node (ref "C22") (pin "+") (pinfunction "+_+") (pintype "passive"))
      (node (ref "C23") (pin "+") (pinfunction "+_+") (pintype "passive"))
      (node (ref "C24") (pin "1") (pinfunction "1_1") (pintype "passive"))
      (node (ref "C4") (pin "1") (pinfunction "1_1") (pintype "passive"))
      (node (ref "CONN1") (pin "PIN2") (pinfunction "VCC_PIN2") (pintype "bidirectional"))
      (node (ref "MOTOR_PREDRIVER") (pin "18") (pinfunction "VBB_18") (pintype "bidirectional"))
      (node (ref "MOTOR_PWR") (pin "PIN2") (pinfunction "VCC_PIN2") (pintype "bidirectional"))
      (node (ref "Q2") (pin "3") (pinfunction "D_3") (pintype "bidirectional"))
      (node (ref "Q4") (pin "3") (pinfunction "D_3") (pintype "bidirectional"))
      (node (ref "Q6") (pin "3") (pinfunction "D_3") (pintype "bidirectional"))
      (node (ref "Q7") (pin "D") (pinfunction "D_D") (pintype "bidirectional"))
      (node (ref "Q7") (pin "S") (pinfunction "S_S") (pintype "bidirectional"))
      (node (ref "S1") (pin "3") (pinfunction "S_3") (pintype "passive"))
      (node (ref "U$5") (pin "+") (pinfunction "+_+") (pintype "bidirectional"))
    )
    (net (code "76") (name "VDD") (class "Default")
      (node (ref "3.3V_REGULATOR") (pin "IN") (pinfunction "IN_IN") (pintype "input"))
      (node (ref "31") (pin "1") (pinfunction "1_1") (pintype "passive"))
      (node (ref "C26") (pin "+") (pinfunction "+_+") (pintype "passive"))
      (node (ref "C27") (pin "+") (pinfunction "+_+") (pintype "passive"))
      (node (ref "C5") (pin "1") (pinfunction "1_1") (pintype "passive"))
      (node (ref "CONN2") (pin "PIN2") (pinfunction "VCC_PIN2") (pintype "bidirectional"))
      (node (ref "CONN3") (pin "PIN2") (pinfunction "VCC_PIN2") (pintype "bidirectional"))
      (node (ref "HALL_SENSOR") (pin "6") (pinfunction "6_6") (pintype "passive"))
      (node (ref "L1") (pin "P$2") (pinfunction "P$2_P$2") (pintype "bidirectional"))
      (node (ref "MCU_PWR") (pin "2") (pinfunction "2_2") (pintype "passive"))
      (node (ref "MOTOR_PREDRIVER") (pin "19") (pinfunction "SPEED_19") (pintype "bidirectional"))
      (node (ref "MOTOR_PREDRIVER") (pin "21") (pinfunction "VDD_21") (pintype "power_in"))
      (node (ref "R15") (pin "1") (pinfunction "1_1") (pintype "passive"))
      (node (ref "R19") (pin "1") (pinfunction "1_1") (pintype "passive"))
      (node (ref "R20") (pin "2") (pinfunction "2_2") (pintype "passive"))
      (node (ref "R34") (pin "1") (pinfunction "1_1") (pintype "passive"))
      (node (ref "R35") (pin "1") (pinfunction "1_1") (pintype "passive"))
      (node (ref "SERVO") (pin "2") (pinfunction "2_2") (pintype "passive"))
    )
    (net (code "77") (name "unconnected-(5VREGULATOR1-ON-Pad7)") (class "Default")
      (node (ref "5VREGULATOR1") (pin "7") (pinfunction "ON_7") (pintype "passive"))
    )
    (net (code "78") (name "unconnected-(DOWN-1.2-Pad2)") (class "Default")
      (node (ref "DOWN") (pin "2") (pinfunction "1.2_2") (pintype "passive"))
    )
    (net (code "79") (name "unconnected-(DOWN-SH-Pad5)") (class "Default")
      (node (ref "DOWN") (pin "5") (pinfunction "SH_5") (pintype "passive"))
    )
    (net (code "80") (name "unconnected-(ESTOP-S-Pad3)") (class "Default")
      (node (ref "ESTOP") (pin "3") (pinfunction "S_3") (pintype "passive"))
    )
    (net (code "81") (name "unconnected-(J1-ADC0_DM0-PadJ2-7)") (class "Default")
      (node (ref "J1") (pin "J2-7") (pinfunction "ADC0_DM0_J2-7") (pintype "bidirectional"))
    )
    (net (code "82") (name "unconnected-(J1-ADC0_DM1-PadJ4-3)") (class "Default")
      (node (ref "J1") (pin "J4-3") (pinfunction "ADC0_DM1_J4-3") (pintype "bidirectional"))
    )
    (net (code "83") (name "unconnected-(J1-ADC0_DP0-PadJ2-5)") (class "Default")
      (node (ref "J1") (pin "J2-5") (pinfunction "ADC0_DP0_J2-5") (pintype "bidirectional"))
    )
    (net (code "84") (name "unconnected-(J1-ADC0_DP1-PadJ4-1)") (class "Default")
      (node (ref "J1") (pin "J4-1") (pinfunction "ADC0_DP1_J4-1") (pintype "bidirectional"))
    )
    (net (code "85") (name "unconnected-(J1-ADC1_DM0-PadJ2-13)") (class "Default")
      (node (ref "J1") (pin "J2-13") (pinfunction "ADC1_DM0_J2-13") (pintype "bidirectional"))
    )
    (net (code "86") (name "unconnected-(J1-ADC1_DM1-PadJ4-7)") (class "Default")
      (node (ref "J1") (pin "J4-7") (pinfunction "ADC1_DM1_J4-7") (pintype "bidirectional"))
    )
    (net (code "87") (name "unconnected-(J1-ADC1_DP0-PadJ2-11)") (class "Default")
      (node (ref "J1") (pin "J2-11") (pinfunction "ADC1_DP0_J2-11") (pintype "bidirectional"))
    )
    (net (code "88") (name "unconnected-(J1-ADC1_DP1-PadJ4-5)") (class "Default")
      (node (ref "J1") (pin "J4-5") (pinfunction "ADC1_DP1_J4-5") (pintype "bidirectional"))
    )
    (net (code "89") (name "unconnected-(J1-ADC1_SE18-PadJ2-17)") (class "Default")
      (node (ref "J1") (pin "J2-17") (pinfunction "ADC1_SE18_J2-17") (pintype "bidirectional"))
    )
    (net (code "90") (name "unconnected-(J1-AREF-PadJ2-16)") (class "Default")
      (node (ref "J1") (pin "J2-16") (pinfunction "AREF_J2-16") (pintype "bidirectional"))
    )
    (net (code "91") (name "unconnected-(J1-DAC0_OUT-PadJ4-11)") (class "Default")
      (node (ref "J1") (pin "J4-11") (pinfunction "DAC0_OUT_J4-11") (pintype "bidirectional"))
    )
    (net (code "92") (name "unconnected-(J1-P3V3_1-PadJ3-4)") (class "Default")
      (node (ref "J1") (pin "J3-4") (pinfunction "P3V3_1_J3-4") (pintype "bidirectional"))
    )
    (net (code "93") (name "unconnected-(J1-P3V3_2-PadJ3-8)") (class "Default")
      (node (ref "J1") (pin "J3-8") (pinfunction "P3V3_2_J3-8") (pintype "bidirectional"))
    )
    (net (code "94") (name "unconnected-(J1-P5V_USB-PadJ3-10)") (class "Default")
      (node (ref "J1") (pin "J3-10") (pinfunction "P5V_USB_J3-10") (pintype "bidirectional"))
    )
    (net (code "95") (name "unconnected-(J1-PTA0-PadJ2-2)") (class "Default")
      (node (ref "J1") (pin "J2-2") (pinfunction "PTA0_J2-2") (pintype "bidirectional"))
    )
    (net (code "96") (name "unconnected-(J1-PTB18-PadJ1-1)") (class "Default")
      (node (ref "J1") (pin "J1-1") (pinfunction "PTB18_J1-1") (pintype "bidirectional"))
    )
    (net (code "97") (name "unconnected-(J1-PTB19-PadJ1-3)") (class "Default")
      (node (ref "J1") (pin "J1-3") (pinfunction "PTB19_J1-3") (pintype "bidirectional"))
    )
    (net (code "98") (name "unconnected-(J1-PTB20-PadJ4-9)") (class "Default")
      (node (ref "J1") (pin "J4-9") (pinfunction "PTB20_J4-9") (pintype "bidirectional"))
    )
    (net (code "99") (name "unconnected-(J1-PTC0-PadJ1-11)") (class "Default")
      (node (ref "J1") (pin "J1-11") (pinfunction "PTC0_J1-11") (pintype "bidirectional"))
    )
    (net (code "100") (name "unconnected-(J1-PTC1-PadJ1-5)") (class "Default")
      (node (ref "J1") (pin "J1-5") (pinfunction "PTC1_J1-5") (pintype "bidirectional"))
    )
    (net (code "101") (name "unconnected-(J1-PTC5-PadJ1-15)") (class "Default")
      (node (ref "J1") (pin "J1-15") (pinfunction "PTC5_J1-15") (pintype "bidirectional"))
    )
    (net (code "102") (name "unconnected-(J1-PTC7-PadJ1-13)") (class "Default")
      (node (ref "J1") (pin "J1-13") (pinfunction "PTC7_J1-13") (pintype "bidirectional"))
    )
    (net (code "103") (name "unconnected-(J1-PTC8-PadJ1-7)") (class "Default")
      (node (ref "J1") (pin "J1-7") (pinfunction "PTC8_J1-7") (pintype "bidirectional"))
    )
    (net (code "104") (name "unconnected-(J1-PTC9-PadJ1-9)") (class "Default")
      (node (ref "J1") (pin "J1-9") (pinfunction "PTC9_J1-9") (pintype "bidirectional"))
    )
    (net (code "105") (name "unconnected-(MOTOR_PREDRIVER-GND-Pad17)") (class "Default")
      (node (ref "MOTOR_PREDRIVER") (pin "17") (pinfunction "GND_17") (pintype "power_in"))
    )
    (net (code "106") (name "unconnected-(RESET-1.2-Pad2)") (class "Default")
      (node (ref "RESET") (pin "2") (pinfunction "1.2_2") (pintype "passive"))
    )
    (net (code "107") (name "unconnected-(RESET-2.2-Pad4)") (class "Default")
      (node (ref "RESET") (pin "4") (pinfunction "2.2_4") (pintype "passive"))
    )
    (net (code "108") (name "unconnected-(RESET-SH-Pad5)") (class "Default")
      (node (ref "RESET") (pin "5") (pinfunction "SH_5") (pintype "passive"))
    )
    (net (code "109") (name "unconnected-(SELECT-1.2-Pad2)") (class "Default")
      (node (ref "SELECT") (pin "2") (pinfunction "1.2_2") (pintype "passive"))
    )
    (net (code "110") (name "unconnected-(SELECT-SH-Pad5)") (class "Default")
      (node (ref "SELECT") (pin "5") (pinfunction "SH_5") (pintype "passive"))
    )
    (net (code "111") (name "unconnected-(SV3-Pad3)") (class "Default")
      (node (ref "SV3") (pin "3") (pinfunction "3_3") (pintype "passive"))
    )
    (net (code "112") (name "unconnected-(SV3-Pad4)") (class "Default")
      (node (ref "SV3") (pin "4") (pinfunction "4_4") (pintype "passive"))
    )
    (net (code "113") (name "unconnected-(SV3-Pad5)") (class "Default")
      (node (ref "SV3") (pin "5") (pinfunction "5_5") (pintype "passive"))
    )
    (net (code "114") (name "unconnected-(SV3-Pad6)") (class "Default")
      (node (ref "SV3") (pin "6") (pinfunction "6_6") (pintype "passive"))
    )
    (net (code "115") (name "unconnected-(SV3-Pad7)") (class "Default")
      (node (ref "SV3") (pin "7") (pinfunction "7_7") (pintype "passive"))
    )
    (net (code "116") (name "unconnected-(SV3-Pad8)") (class "Default")
      (node (ref "SV3") (pin "8") (pinfunction "8_8") (pintype "passive"))
    )
    (net (code "117") (name "unconnected-(SV3-Pad9)") (class "Default")
      (node (ref "SV3") (pin "9") (pinfunction "9_9") (pintype "passive"))
    )
    (net (code "118") (name "unconnected-(SV3-Pad10)") (class "Default")
      (node (ref "SV3") (pin "10") (pinfunction "10_10") (pintype "passive"))
    )
    (net (code "119") (name "unconnected-(SV3-Pad11)") (class "Default")
      (node (ref "SV3") (pin "11") (pinfunction "11_11") (pintype "passive"))
    )
    (net (code "120") (name "unconnected-(SV3-Pad12)") (class "Default")
      (node (ref "SV3") (pin "12") (pinfunction "12_12") (pintype "passive"))
    )
    (net (code "121") (name "unconnected-(SV3-Pad13)") (class "Default")
      (node (ref "SV3") (pin "13") (pinfunction "13_13") (pintype "passive"))
    )
    (net (code "122") (name "unconnected-(SV3-Pad14)") (class "Default")
      (node (ref "SV3") (pin "14") (pinfunction "14_14") (pintype "passive"))
    )
    (net (code "123") (name "unconnected-(SV4-Pad3)") (class "Default")
      (node (ref "SV4") (pin "3") (pinfunction "3_3") (pintype "passive"))
    )
    (net (code "124") (name "unconnected-(SV4-Pad4)") (class "Default")
      (node (ref "SV4") (pin "4") (pinfunction "4_4") (pintype "passive"))
    )
    (net (code "125") (name "unconnected-(SV4-Pad5)") (class "Default")
      (node (ref "SV4") (pin "5") (pinfunction "5_5") (pintype "passive"))
    )
    (net (code "126") (name "unconnected-(SV4-Pad6)") (class "Default")
      (node (ref "SV4") (pin "6") (pinfunction "6_6") (pintype "passive"))
    )
    (net (code "127") (name "unconnected-(SV4-Pad7)") (class "Default")
      (node (ref "SV4") (pin "7") (pinfunction "7_7") (pintype "passive"))
    )
    (net (code "128") (name "unconnected-(SV4-Pad8)") (class "Default")
      (node (ref "SV4") (pin "8") (pinfunction "8_8") (pintype "passive"))
    )
    (net (code "129") (name "unconnected-(SV4-Pad9)") (class "Default")
      (node (ref "SV4") (pin "9") (pinfunction "9_9") (pintype "passive"))
    )
    (net (code "130") (name "unconnected-(SV4-Pad10)") (class "Default")
      (node (ref "SV4") (pin "10") (pinfunction "10_10") (pintype "passive"))
    )
    (net (code "131") (name "unconnected-(SV4-Pad11)") (class "Default")
      (node (ref "SV4") (pin "11") (pinfunction "11_11") (pintype "passive"))
    )
    (net (code "132") (name "unconnected-(SV4-Pad12)") (class "Default")
      (node (ref "SV4") (pin "12") (pinfunction "12_12") (pintype "passive"))
    )
    (net (code "133") (name "unconnected-(SV4-Pad13)") (class "Default")
      (node (ref "SV4") (pin "13") (pinfunction "13_13") (pintype "passive"))
    )
    (net (code "134") (name "unconnected-(SV4-Pad14)") (class "Default")
      (node (ref "SV4") (pin "14") (pinfunction "14_14") (pintype "passive"))
    )
    (net (code "135") (name "unconnected-(UP-1.2-Pad2)") (class "Default")
      (node (ref "UP") (pin "2") (pinfunction "1.2_2") (pintype "passive"))
    )
    (net (code "136") (name "unconnected-(UP-SH-Pad5)") (class "Default")
      (node (ref "UP") (pin "5") (pinfunction "SH_5") (pintype "passive"))
    )
  )
)
